# shoff_900_T36-12.net
KiCad netlist of a schematic drawn in EAGLE
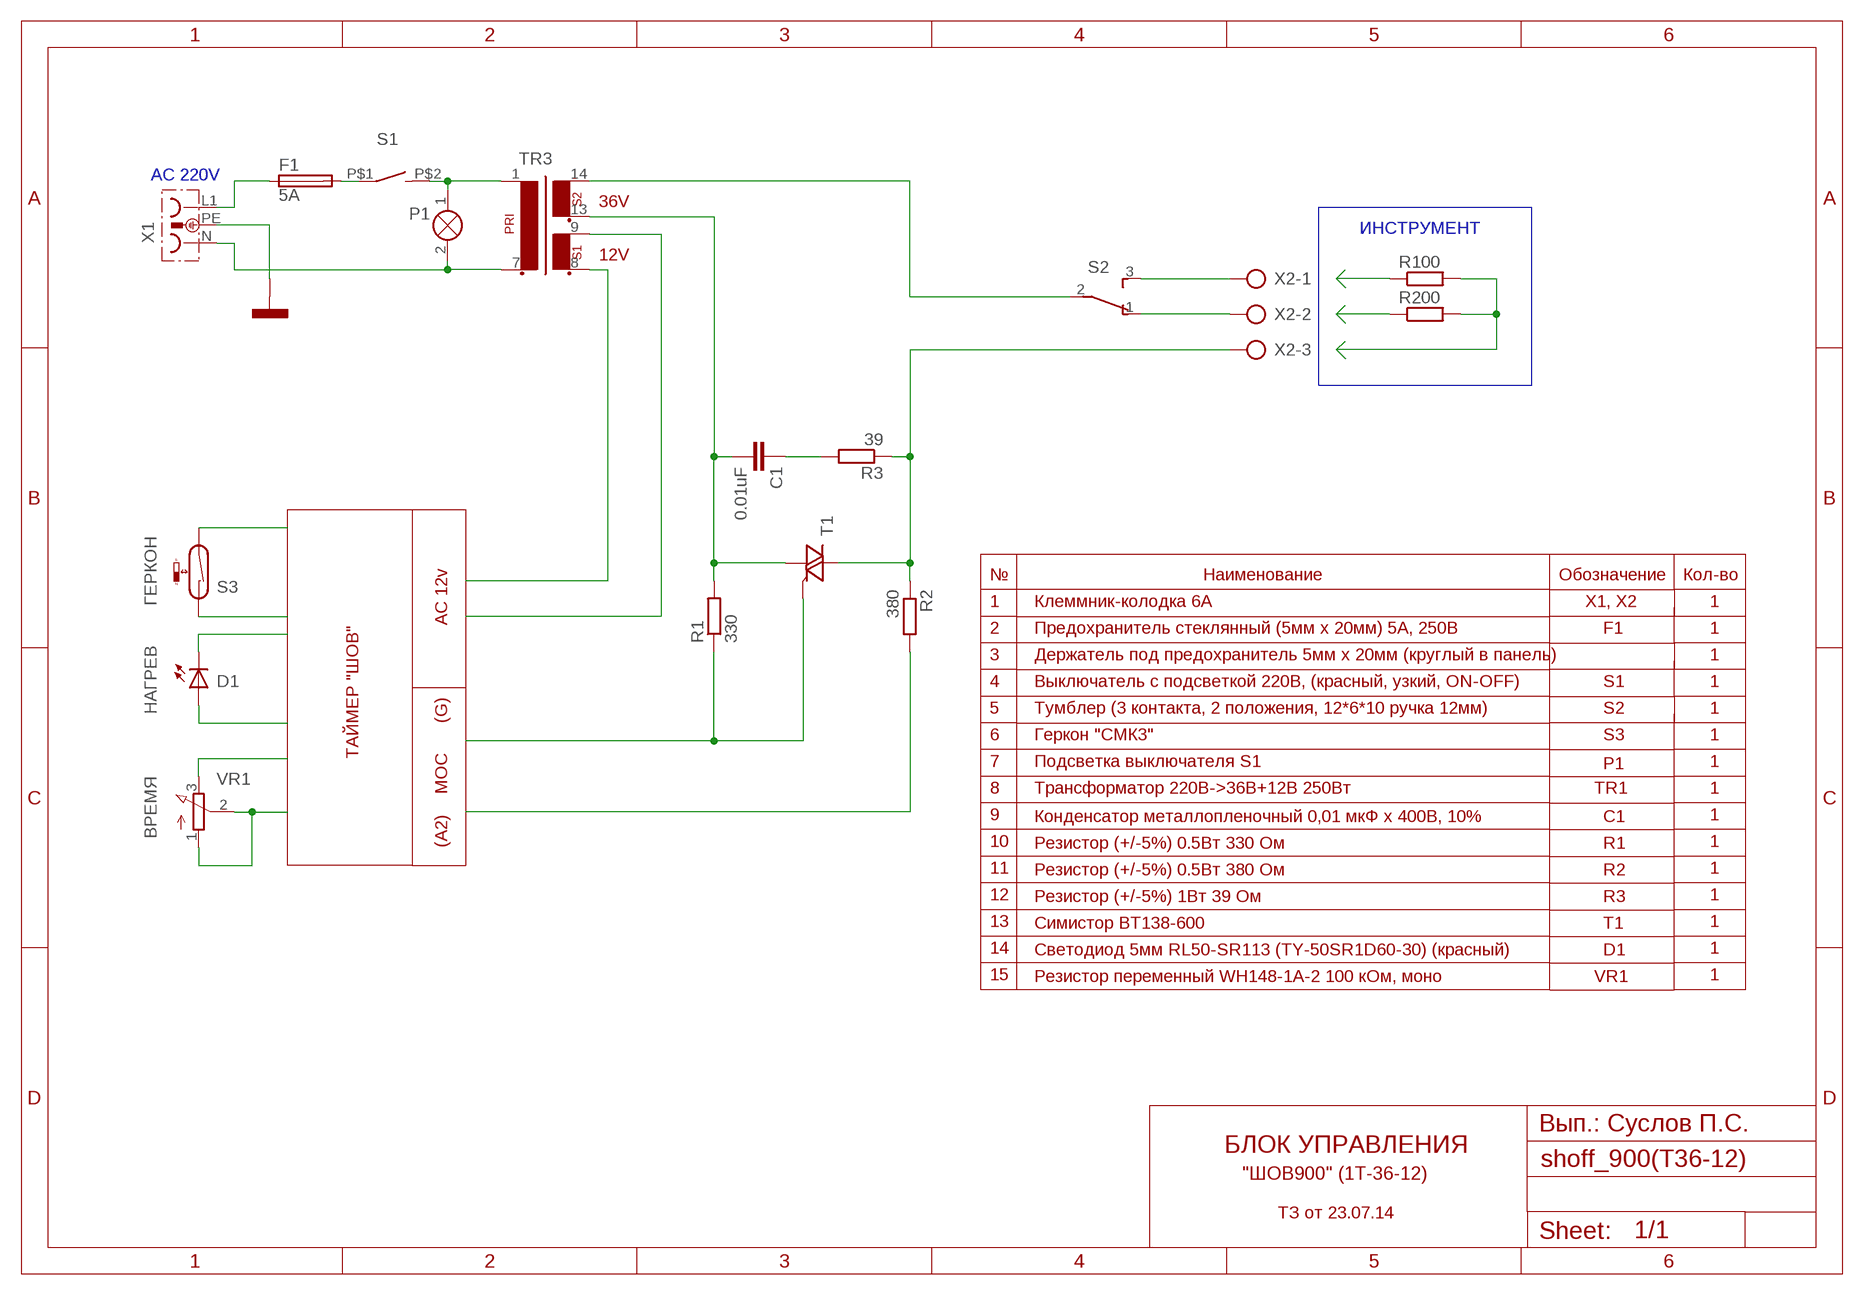
[diagram p0: schematic, sheet 1]

(export (version "E")
  (design (tool "Eeschema 10.0.6"))
  (components
    (comp (ref "C1")
      (value "0.01uF")
      (footprint "eagle-import:C025-030X050")
      (libsource (lib "eagle-import") (part "C-EU025-030X050"))
    )
    (comp (ref "F1")
      (value "5A")
      (footprint "eagle-import:GSH15")
      (fields (field (name "MPN") "64900001039"))
      (libsource (lib "eagle-import") (part "GSH15"))
    )
    (comp (ref "GG")
      (value "MASSE_ALLGEMEIN")
      (footprint "eagle-import:MASSE_ALLGEMEIN")
      (libsource (lib "eagle-import") (part "MASSE_ALLGEMEIN"))
    )
    (comp (ref "P1")
      (value "SIGNALLAMPE")
      (footprint "eagle-import:LAMPE")
      (libsource (lib "eagle-import") (part "SIGNALLAMPE"))
    )
    (comp (ref "R1")
      (value "330")
      (footprint "eagle-import:0207_5V")
      (libsource (lib "eagle-import") (part "R-EU_0207/5V"))
    )
    (comp (ref "R2")
      (value "380")
      (footprint "eagle-import:0207_5V")
      (libsource (lib "eagle-import") (part "R-EU_0207/5V"))
    )
    (comp (ref "R3")
      (value "39")
      (footprint "eagle-import:0207_5V")
      (libsource (lib "eagle-import") (part "R-EU_0207/5V"))
    )
    (comp (ref "R100")
      (value "R-EU_R0201")
      (footprint "eagle-import:R0201")
      (libsource (lib "eagle-import") (part "R-EU_R0201"))
    )
    (comp (ref "R200")
      (value "R-EU_R0201")
      (footprint "eagle-import:R0201")
      (libsource (lib "eagle-import") (part "R-EU_R0201"))
    )
    (comp (ref "S1")
      (value "SCHLIESSER_ARBEITSKONTAKT")
      (footprint "eagle-import:1")
      (libsource (lib "eagle-import") (part "SCHLIESSER_ARBEITSKONTAKT"))
    )
    (comp (ref "S2")
      (value "TL36WO")
      (footprint "eagle-import:TL3XWO")
      (libsource (lib "eagle-import") (part "TL36WO"))
    )
    (comp (ref "S3")
      (value "ГЕРКОН")
      (footprint "eagle-import:CT10-G1")
      (fields (field (name "MF") "COTO TECHNOLOGY") (field (name "MPN") "CT10-1530-G1"))
      (libsource (lib "eagle-import") (part "REED-SWITCH-CT10-1530-G1"))
    )
    (comp (ref "T1")
      (value "BTA26-V")
      (footprint "eagle-import:TOP3S-1")
      (libsource (lib "eagle-import") (part "BTA26-V"))
    )
    (comp (ref "TR3")
      (value "BV054-5387.0K")
      (footprint "eagle-import:EI54-18,8_16VA")
      (libsource (lib "eagle-import") (part "BV054-5387.0K"))
    )
    (comp (ref "X1")
      (value "STECKDOSE")
      (footprint "eagle-import:STECKDOSE")
      (libsource (lib "eagle-import") (part "STECKDOSE"))
    )
    (comp (ref "X2")
      (value "AK500/3")
      (footprint "eagle-import:AK500_3")
      (libsource (lib "eagle-import") (part "AK500/3"))
    )
    (comp (ref "ВРЕМЯ")
      (value "3RP/1610N")
      (footprint "eagle-import:3RP_1610N")
      (libsource (lib "eagle-import") (part "3RP/1610N"))
    )
    (comp (ref "ГОТОВ")
      (value "НАГРЕВ")
      (footprint "eagle-import:LED5MM")
      (libsource (lib "eagle-import") (part "LED5MM"))
    )
  )
  (nets
    (net (code "1") (name "Net-(C1-Pad1)") (class "Default")
      (node (ref "C1") (pin "1") (pinfunction "1_1") (pintype "passive"))
      (node (ref "R3") (pin "2") (pinfunction "2_2") (pintype "passive"))
    )
    (net (code "2") (name "Net-(F1-Pad1)") (class "Default")
      (node (ref "F1") (pin "1") (pinfunction "1_1") (pintype "passive"))
      (node (ref "X1") (pin "L1") (pinfunction "L1_L1") (pintype "passive"))
    )
    (net (code "3") (name "Net-(GG-0V)") (class "Default")
      (node (ref "GG") (pin "1") (pinfunction "0V_1") (pintype "passive"))
      (node (ref "X1") (pin "PE") (pinfunction "PE_PE") (pintype "passive"))
    )
    (net (code "4") (name "Net-(P1-X1)") (class "Default")
      (node (ref "P1") (pin "1") (pinfunction "X1_1") (pintype "passive"))
      (node (ref "S1") (pin "P$2") (pinfunction "3_P$2") (pintype "passive"))
      (node (ref "TR3") (pin "1") (pinfunction "1_1") (pintype "passive"))
    )
    (net (code "5") (name "Net-(P1-X2)") (class "Default")
      (node (ref "P1") (pin "2") (pinfunction "X2_2") (pintype "passive"))
      (node (ref "TR3") (pin "7") (pinfunction "2_7") (pintype "passive"))
      (node (ref "X1") (pin "N") (pinfunction "N_N") (pintype "passive"))
    )
    (net (code "6") (name "Net-(R1-Pad1)") (class "Default")
      (node (ref "R1") (pin "1") (pinfunction "1_1") (pintype "passive"))
      (node (ref "T1") (pin "G") (pinfunction "G_G") (pintype "passive"))
    )
    (net (code "7") (name "Net-(R100-Pad2)") (class "Default")
      (node (ref "R100") (pin "2") (pinfunction "2_2") (pintype "passive"))
      (node (ref "R200") (pin "2") (pinfunction "2_2") (pintype "passive"))
    )
    (net (code "8") (name "Net-(S1-4)") (class "Default")
      (node (ref "F1") (pin "2") (pinfunction "2_2") (pintype "passive"))
      (node (ref "S1") (pin "P$1") (pinfunction "4_P$1") (pintype "passive"))
    )
    (net (code "9") (name "Net-(S2-O)") (class "Default")
      (node (ref "S2") (pin "1") (pinfunction "O_1") (pintype "passive"))
      (node (ref "X2") (pin "2") (pinfunction "KL_2") (pintype "passive"))
    )
    (net (code "10") (name "Net-(S2-P)") (class "Default")
      (node (ref "S2") (pin "2") (pinfunction "P_2") (pintype "passive"))
      (node (ref "TR3") (pin "14") (pinfunction "6_14") (pintype "passive"))
    )
    (net (code "11") (name "Net-(S2-S)") (class "Default")
      (node (ref "S2") (pin "3") (pinfunction "S_3") (pintype "passive"))
      (node (ref "X2") (pin "1") (pinfunction "KL_1") (pintype "passive"))
    )
    (net (code "12") (name "Net-(TR3-5)") (class "Default")
      (node (ref "C1") (pin "2") (pinfunction "2_2") (pintype "passive"))
      (node (ref "R1") (pin "2") (pinfunction "2_2") (pintype "passive"))
      (node (ref "T1") (pin "A1") (pinfunction "A1_A1") (pintype "passive"))
      (node (ref "TR3") (pin "13") (pinfunction "5_13") (pintype "passive"))
    )
    (net (code "13") (name "Net-(X2C-KL)") (class "Default")
      (node (ref "R2") (pin "1") (pinfunction "1_1") (pintype "passive"))
      (node (ref "R3") (pin "1") (pinfunction "1_1") (pintype "passive"))
      (node (ref "T1") (pin "A2") (pinfunction "A2_A2") (pintype "passive"))
      (node (ref "X2") (pin "3") (pinfunction "KL_3") (pintype "passive"))
    )
    (net (code "14") (name "Net-(ВРЕМЯ-A)") (class "Default")
      (node (ref "ВРЕМЯ") (pin "1") (pinfunction "A_1") (pintype "passive"))
      (node (ref "ВРЕМЯ") (pin "2") (pinfunction "S_2") (pintype "passive"))
    )
    (net (code "15") (name "unconnected-(R2-Pad2)") (class "Default")
      (node (ref "R2") (pin "2") (pinfunction "2_2") (pintype "passive"))
    )
    (net (code "16") (name "unconnected-(R100-Pad1)") (class "Default")
      (node (ref "R100") (pin "1") (pinfunction "1_1") (pintype "passive"))
    )
    (net (code "17") (name "unconnected-(R200-Pad1)") (class "Default")
      (node (ref "R200") (pin "1") (pinfunction "1_1") (pintype "passive"))
    )
    (net (code "18") (name "unconnected-(S3-Pad1)") (class "Default")
      (node (ref "S3") (pin "1") (pinfunction "1_1") (pintype "passive"))
    )
    (net (code "19") (name "unconnected-(S3-Pad2)") (class "Default")
      (node (ref "S3") (pin "2") (pinfunction "2_2") (pintype "passive"))
    )
    (net (code "20") (name "unconnected-(TR3-3-Pad8)") (class "Default")
      (node (ref "TR3") (pin "8") (pinfunction "3_8") (pintype "passive"))
    )
    (net (code "21") (name "unconnected-(TR3-4-Pad9)") (class "Default")
      (node (ref "TR3") (pin "9") (pinfunction "4_9") (pintype "passive"))
    )
    (net (code "22") (name "unconnected-(ВРЕМЯ-E-Pad3)") (class "Default")
      (node (ref "ВРЕМЯ") (pin "3") (pinfunction "E_3") (pintype "passive"))
    )
    (net (code "23") (name "unconnected-(ГОТОВ-C-PadK)") (class "Default")
      (node (ref "ГОТОВ") (pin "K") (pinfunction "C_K") (pintype "passive"))
    )
    (net (code "24") (name "unconnected-(ГОТОВ-PadA)") (class "Default")
      (node (ref "ГОТОВ") (pin "A") (pinfunction "A_A") (pintype "passive"))
    )
  )
)
